# Sij.net
KiCad netlist of a schematic drawn in EAGLE
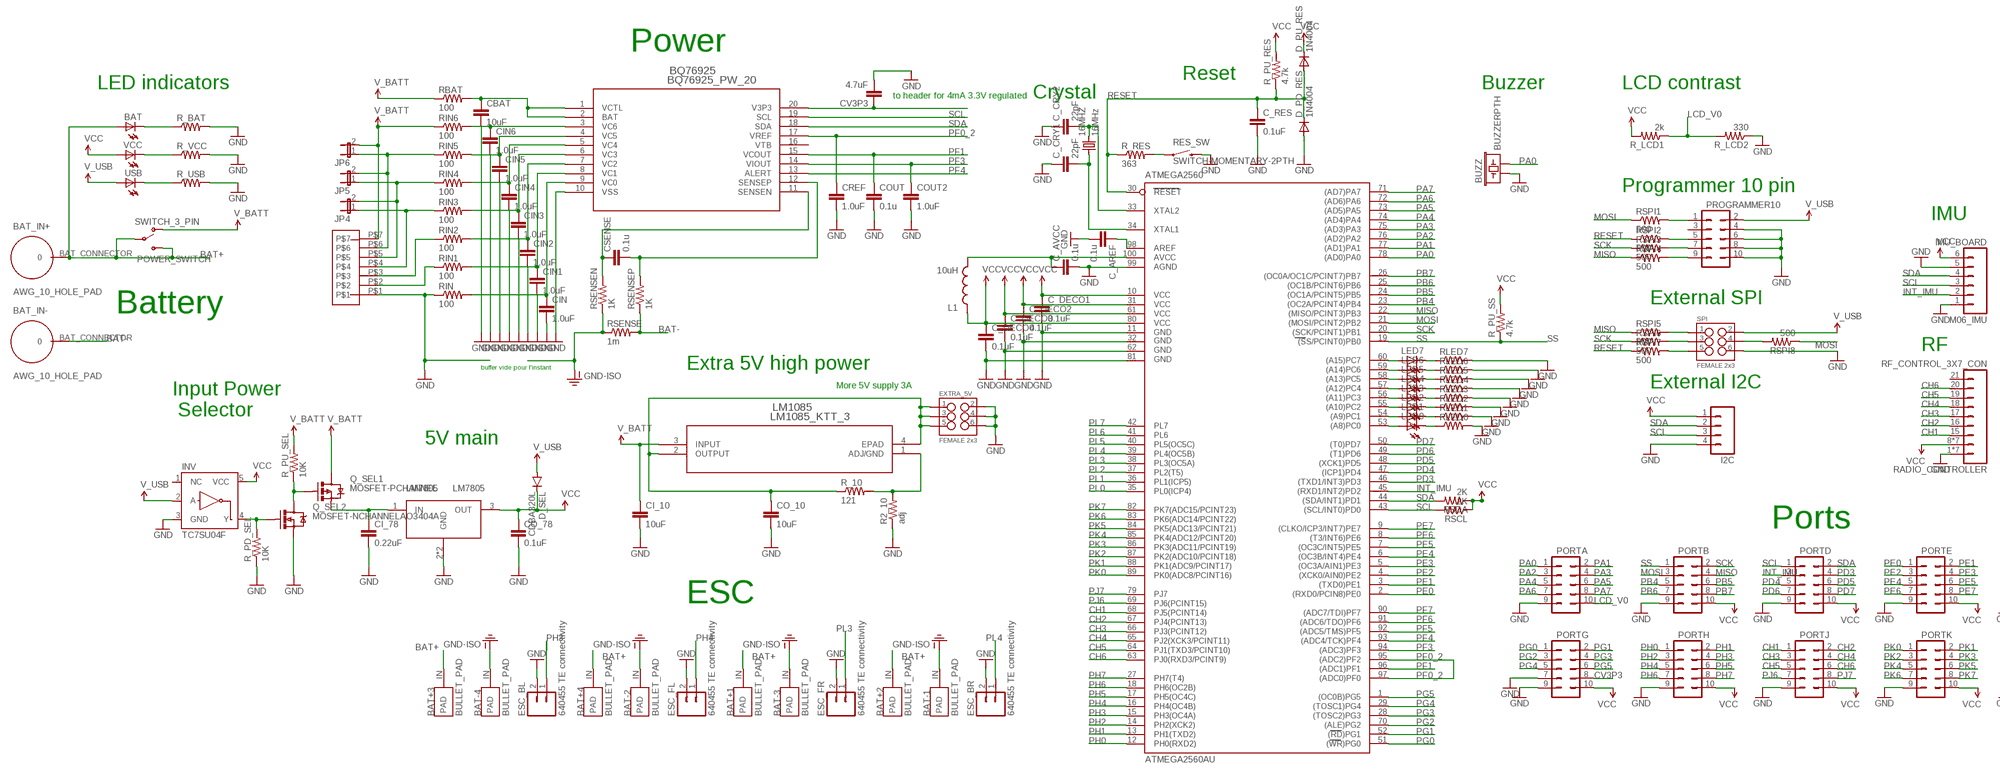
[diagram p0: schematic, sheet 1, part 1 of 2]
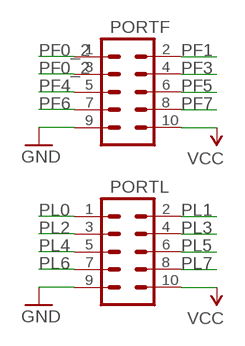
[diagram p1: schematic, sheet 1, part 2 of 2]

(export (version "E")
  (design (tool "Eeschema 10.0.6"))
  (components
    (comp (ref "16MHZ")
      (value "16MHz")
      (footprint "eagle-import:HC49US")
      (libsource (lib "eagle-import") (part "CRYSTALHC49US"))
    )
    (comp (ref "ATMEGA2560")
      (value "ATMEGA2560AU")
      (footprint "eagle-import:TQFP100")
      (libsource (lib "eagle-import") (part "ATMEGA2560AU"))
    )
    (comp (ref "BAT")
      (value "LEDCHIPLED_0805")
      (footprint "eagle-import:CHIPLED_0805")
      (libsource (lib "eagle-import") (part "LEDCHIPLED_0805"))
    )
    (comp (ref "BAT+1")
      (value "BULLET_PAD")
      (footprint "eagle-import:4.5MM_SQUARE")
      (libsource (lib "eagle-import") (part "BULLET_PAD"))
    )
    (comp (ref "BAT+2")
      (value "BULLET_PAD")
      (footprint "eagle-import:4.5MM_SQUARE")
      (libsource (lib "eagle-import") (part "BULLET_PAD"))
    )
    (comp (ref "BAT+3")
      (value "BULLET_PAD")
      (footprint "eagle-import:4.5MM_SQUARE")
      (libsource (lib "eagle-import") (part "BULLET_PAD"))
    )
    (comp (ref "BAT+4")
      (value "BULLET_PAD")
      (footprint "eagle-import:4.5MM_SQUARE")
      (libsource (lib "eagle-import") (part "BULLET_PAD"))
    )
    (comp (ref "BAT-1")
      (value "BULLET_PAD")
      (footprint "eagle-import:4.5MM_SQUARE")
      (libsource (lib "eagle-import") (part "BULLET_PAD"))
    )
    (comp (ref "BAT-2")
      (value "BULLET_PAD")
      (footprint "eagle-import:4.5MM_SQUARE")
      (libsource (lib "eagle-import") (part "BULLET_PAD"))
    )
    (comp (ref "BAT-3")
      (value "BULLET_PAD")
      (footprint "eagle-import:4.5MM_SQUARE")
      (libsource (lib "eagle-import") (part "BULLET_PAD"))
    )
    (comp (ref "BAT-4")
      (value "BULLET_PAD")
      (footprint "eagle-import:4.5MM_SQUARE")
      (libsource (lib "eagle-import") (part "BULLET_PAD"))
    )
    (comp (ref "BAT-MONIT")
      (value "7_PIN_JST-XH")
      (footprint "eagle-import:7_PIN_JST-XH")
      (libsource (lib "eagle-import") (part "7_PIN_JST-XH"))
    )
    (comp (ref "BAT_IN+")
      (value "AWG_10_HOLE_PAD")
      (footprint "eagle-import:AWG10_HOLE_PAD")
      (libsource (lib "eagle-import") (part "AWG_10_HOLE_PAD"))
    )
    (comp (ref "BAT_IN-")
      (value "AWG_10_HOLE_PAD")
      (footprint "eagle-import:AWG10_HOLE_PAD")
      (libsource (lib "eagle-import") (part "AWG_10_HOLE_PAD"))
    )
    (comp (ref "BQ76925")
      (value "BQ76925_PW_20")
      (footprint "eagle-import:PW20")
      (fields
        (field (name "GENERIC_PART_NUMBER") "BQ76925")
        (field (name "MANUFACTURER") "Texas Instruments")
        (field (name "MANUFACTURER_PART_NUMBER") "bq76925_pw_20")
      )
      (libsource (lib "eagle-import") (part "BQ76925_PW_20"))
    )
    (comp (ref "BUZZ")
      (value "BUZZERPTH")
      (footprint "eagle-import:BUZZER-12MM")
      (libsource (lib "eagle-import") (part "BUZZERPTH"))
    )
    (comp (ref "CBAT")
      (value "10uF")
      (footprint "eagle-import:0805")
      (libsource (lib "eagle-import") (part "CAP0805"))
    )
    (comp (ref "CIN")
      (value "1.0uF")
      (footprint "eagle-import:0603-CAP")
      (libsource (lib "eagle-import") (part "1.0UF-16V-10%(0603)"))
    )
    (comp (ref "CIN1")
      (value "1.0uF")
      (footprint "eagle-import:0603-CAP")
      (libsource (lib "eagle-import") (part "1.0UF-16V-10%(0603)"))
    )
    (comp (ref "CIN2")
      (value "1.0uF")
      (footprint "eagle-import:0603-CAP")
      (libsource (lib "eagle-import") (part "1.0UF-16V-10%(0603)"))
    )
    (comp (ref "CIN3")
      (value "1.0uF")
      (footprint "eagle-import:0603-CAP")
      (libsource (lib "eagle-import") (part "1.0UF-16V-10%(0603)"))
    )
    (comp (ref "CIN4")
      (value "1.0uF")
      (footprint "eagle-import:0603-CAP")
      (libsource (lib "eagle-import") (part "1.0UF-16V-10%(0603)"))
    )
    (comp (ref "CIN5")
      (value "1.0uF")
      (footprint "eagle-import:0603-CAP")
      (libsource (lib "eagle-import") (part "1.0UF-16V-10%(0603)"))
    )
    (comp (ref "CIN6")
      (value "1.0uF")
      (footprint "eagle-import:0603-CAP")
      (libsource (lib "eagle-import") (part "1.0UF-16V-10%(0603)"))
    )
    (comp (ref "CI_10")
      (value "10uF")
      (footprint "eagle-import:0805")
      (libsource (lib "eagle-import") (part "22UF-6.3V-20%(0805)"))
    )
    (comp (ref "CI_78")
      (value "0.22uF")
      (footprint "eagle-import:0603-CAP")
      (libsource (lib "eagle-import") (part "0.22UF-25V-10%(0603)"))
    )
    (comp (ref "COUT")
      (value "0.1u")
      (footprint "eagle-import:0603-CAP")
      (libsource (lib "eagle-import") (part "CAP0603-CAP"))
    )
    (comp (ref "COUT2")
      (value "1.0uF")
      (footprint "eagle-import:0603-CAP")
      (libsource (lib "eagle-import") (part "1.0UF-16V-10%(0603)"))
    )
    (comp (ref "CO_10")
      (value "10uF")
      (footprint "eagle-import:1206")
      (libsource (lib "eagle-import") (part "CAP1206"))
    )
    (comp (ref "CO_78")
      (value "0.1uF")
      (footprint "eagle-import:0603-CAP")
      (libsource (lib "eagle-import") (part "0.1UF-25V-5%(0603)"))
    )
    (comp (ref "CREF")
      (value "1.0uF")
      (footprint "eagle-import:0603-CAP")
      (libsource (lib "eagle-import") (part "1.0UF-16V-10%(0603)"))
    )
    (comp (ref "CSENSE")
      (value "0.1u")
      (footprint "eagle-import:0603-CAP")
      (libsource (lib "eagle-import") (part "SparkFun-Passives_CAP0603-CAP"))
    )
    (comp (ref "CV3P3")
      (value "4.7uF")
      (footprint "eagle-import:0603-CAP")
      (libsource (lib "eagle-import") (part "4.7UF-6.3V-10%(0603)0603"))
    )
    (comp (ref "C_AREF")
      (value "0.1u")
      (footprint "eagle-import:0603-CAP")
      (libsource (lib "eagle-import") (part "CAP0603-CAP"))
    )
    (comp (ref "C_AVCC")
      (value "0.1u")
      (footprint "eagle-import:0603-CAP")
      (libsource (lib "eagle-import") (part "CAP0603-CAP"))
    )
    (comp (ref "C_CRY1")
      (value "22pF")
      (footprint "eagle-import:0603-CAP")
      (libsource (lib "eagle-import") (part "22PF-50V-5%(0603)"))
    )
    (comp (ref "C_CRY2")
      (value "22pF")
      (footprint "eagle-import:0603-CAP")
      (libsource (lib "eagle-import") (part "22PF-50V-5%(0603)"))
    )
    (comp (ref "C_DECO1")
      (value "0.1uF")
      (footprint "eagle-import:0603-CAP")
      (libsource (lib "eagle-import") (part "0.1UF-25V-5%(0603)"))
    )
    (comp (ref "C_DECO2")
      (value "0.1uF")
      (footprint "eagle-import:0603-CAP")
      (libsource (lib "eagle-import") (part "0.1UF-25V-5%(0603)"))
    )
    (comp (ref "C_DECO3")
      (value "0.1uF")
      (footprint "eagle-import:0603-CAP")
      (libsource (lib "eagle-import") (part "0.1UF-25V-5%(0603)"))
    )
    (comp (ref "C_DECO4")
      (value "0.1uF")
      (footprint "eagle-import:0603-CAP")
      (libsource (lib "eagle-import") (part "0.1UF-25V-5%(0603)"))
    )
    (comp (ref "C_RES")
      (value "0.1uF")
      (footprint "eagle-import:0603-CAP")
      (libsource (lib "eagle-import") (part "0.1UF-25V-5%(0603)"))
    )
    (comp (ref "D_PD_RES")
      (value "1N4004")
      (footprint "eagle-import:DO41-10")
      (libsource (lib "eagle-import") (part "1N4004"))
    )
    (comp (ref "D_PU_RES")
      (value "1N4004")
      (footprint "eagle-import:DO41-10")
      (libsource (lib "eagle-import") (part "1N4004"))
    )
    (comp (ref "D_SEL")
      (value "CDBA320L")
      (footprint "eagle-import:SMA-DIODE_ALT")
      (libsource (lib "eagle-import") (part "DIODESMA-ALT"))
    )
    (comp (ref "ESC_BL")
      (value "640455 TE connectivity")
      (footprint "eagle-import:1X02")
      (libsource (lib "eagle-import") (part "M02PTH"))
    )
    (comp (ref "ESC_BR")
      (value "640455 TE connectivity")
      (footprint "eagle-import:1X02")
      (libsource (lib "eagle-import") (part "M02PTH"))
    )
    (comp (ref "ESC_FL")
      (value "640455 TE connectivity")
      (footprint "eagle-import:1X02")
      (libsource (lib "eagle-import") (part "M02PTH"))
    )
    (comp (ref "ESC_FR")
      (value "640455 TE connectivity")
      (footprint "eagle-import:1X02")
      (libsource (lib "eagle-import") (part "M02PTH"))
    )
    (comp (ref "EXTRA_5V")
      (value "FEMALE 2x3")
      (footprint "eagle-import:2X3")
      (libsource (lib "eagle-import") (part "M03X2FEMALE"))
    )
    (comp (ref "I2C")
      (value "M041X04_NO_SILK")
      (footprint "eagle-import:1X04_NO_SILK")
      (libsource (lib "eagle-import") (part "M041X04_NO_SILK"))
    )
    (comp (ref "IMU_BOARD")
      (value "M06_IMU")
      (footprint "eagle-import:1X06_LONGPADS")
      (libsource (lib "eagle-import") (part "M06_IMU"))
    )
    (comp (ref "INV")
      (value "TC7SU04F")
      (footprint "eagle-import:SOT23-5")
      (libsource (lib "eagle-import") (part "INVERTER_SOT23-5"))
    )
    (comp (ref "JP4")
      (value "JUMPER-2PTH")
      (footprint "eagle-import:1X02")
      (libsource (lib "eagle-import") (part "JUMPER-2PTH"))
    )
    (comp (ref "JP5")
      (value "JUMPER-2PTH")
      (footprint "eagle-import:1X02")
      (libsource (lib "eagle-import") (part "JUMPER-2PTH"))
    )
    (comp (ref "JP6")
      (value "JUMPER-2PTH")
      (footprint "eagle-import:1X02")
      (libsource (lib "eagle-import") (part "JUMPER-2PTH"))
    )
    (comp (ref "L1")
      (value "10uH")
      (footprint "eagle-import:0805")
      (libsource (lib "eagle-import") (part "INDUCTOR0805"))
    )
    (comp (ref "LED0")
      (value "LEDCHIPLED_0805")
      (footprint "eagle-import:CHIPLED_0805")
      (libsource (lib "eagle-import") (part "LEDCHIPLED_0805"))
    )
    (comp (ref "LED1")
      (value "LEDCHIPLED_0805")
      (footprint "eagle-import:CHIPLED_0805")
      (libsource (lib "eagle-import") (part "LEDCHIPLED_0805"))
    )
    (comp (ref "LED2")
      (value "LEDCHIPLED_0805")
      (footprint "eagle-import:CHIPLED_0805")
      (libsource (lib "eagle-import") (part "LEDCHIPLED_0805"))
    )
    (comp (ref "LED3")
      (value "LEDCHIPLED_0805")
      (footprint "eagle-import:CHIPLED_0805")
      (libsource (lib "eagle-import") (part "LEDCHIPLED_0805"))
    )
    (comp (ref "LED4")
      (value "LEDCHIPLED_0805")
      (footprint "eagle-import:CHIPLED_0805")
      (libsource (lib "eagle-import") (part "LEDCHIPLED_0805"))
    )
    (comp (ref "LED5")
      (value "LEDCHIPLED_0805")
      (footprint "eagle-import:CHIPLED_0805")
      (libsource (lib "eagle-import") (part "LEDCHIPLED_0805"))
    )
    (comp (ref "LED6")
      (value "LEDCHIPLED_0805")
      (footprint "eagle-import:CHIPLED_0805")
      (libsource (lib "eagle-import") (part "LEDCHIPLED_0805"))
    )
    (comp (ref "LED7")
      (value "LEDCHIPLED_0805")
      (footprint "eagle-import:CHIPLED_0805")
      (libsource (lib "eagle-import") (part "LEDCHIPLED_0805"))
    )
    (comp (ref "LM1085")
      (value "LM1085_KTT_3")
      (footprint "eagle-import:KTT3")
      (fields (field (name "MANUFACTURER_PART_NUMBER") "lm1085_ktt_3"))
      (libsource (lib "eagle-import") (part "LM1085_KTT_3"))
    )
    (comp (ref "LM7805")
      (value "LM7805")
      (footprint "eagle-import:KTT3")
      (libsource (lib "eagle-import") (part "LM7805"))
    )
    (comp (ref "PORTA")
      (value "M05X2PTH")
      (footprint "eagle-import:AVR_ICSP")
      (libsource (lib "eagle-import") (part "M05X2PTH"))
    )
    (comp (ref "PORTB")
      (value "M05X2PTH")
      (footprint "eagle-import:AVR_ICSP")
      (libsource (lib "eagle-import") (part "M05X2PTH"))
    )
    (comp (ref "PORTD")
      (value "M05X2PTH")
      (footprint "eagle-import:AVR_ICSP")
      (libsource (lib "eagle-import") (part "M05X2PTH"))
    )
    (comp (ref "PORTE")
      (value "M05X2PTH")
      (footprint "eagle-import:AVR_ICSP")
      (libsource (lib "eagle-import") (part "M05X2PTH"))
    )
    (comp (ref "PORTF")
      (value "M05X2PTH")
      (footprint "eagle-import:AVR_ICSP")
      (libsource (lib "eagle-import") (part "M05X2PTH"))
    )
    (comp (ref "PORTG")
      (value "M05X2PTH")
      (footprint "eagle-import:AVR_ICSP")
      (libsource (lib "eagle-import") (part "M05X2PTH"))
    )
    (comp (ref "PORTH")
      (value "M05X2PTH")
      (footprint "eagle-import:AVR_ICSP")
      (libsource (lib "eagle-import") (part "M05X2PTH"))
    )
    (comp (ref "PORTJ")
      (value "M05X2PTH")
      (footprint "eagle-import:AVR_ICSP")
      (libsource (lib "eagle-import") (part "M05X2PTH"))
    )
    (comp (ref "PORTK")
      (value "M05X2PTH")
      (footprint "eagle-import:AVR_ICSP")
      (libsource (lib "eagle-import") (part "M05X2PTH"))
    )
    (comp (ref "PORTL")
      (value "M05X2PTH")
      (footprint "eagle-import:AVR_ICSP")
      (libsource (lib "eagle-import") (part "M05X2PTH"))
    )
    (comp (ref "POWER_SWITCH")
      (value "SWITCH_3_PIN")
      (footprint "eagle-import:SWITCH-SPDT_KIT")
      (libsource (lib "eagle-import") (part "SWITCH_3_PIN"))
    )
    (comp (ref "PROGRAMMER10")
      (value "M05X2PTH")
      (footprint "eagle-import:AVR_ICSP")
      (libsource (lib "eagle-import") (part "M05X2PTH"))
    )
    (comp (ref "Q_SEL1")
      (value "MOSFET-PCHANNEL")
      (footprint "eagle-import:SOT23-3")
      (libsource (lib "eagle-import") (part "MOSFET-PCHANNEL"))
    )
    (comp (ref "Q_SEL2")
      (value "MOSFET-NCHANNELAO3404A")
      (footprint "eagle-import:SOT23-3")
      (libsource (lib "eagle-import") (part "MOSFET-NCHANNELAO3404A"))
    )
    (comp (ref "R2_10")
      (value "adj")
      (footprint "eagle-import:R0603")
      (libsource (lib "eagle-import") (part "R-US_R0603"))
    )
    (comp (ref "RADIO_CONTROLLER")
      (value "RF_CONTROL_3X7_CON")
      (footprint "eagle-import:3X07")
      (libsource (lib "eagle-import") (part "RF_CONTROL_3X7_CON"))
    )
    (comp (ref "RBAT")
      (value "100")
      (footprint "eagle-import:R0603")
      (libsource (lib "eagle-import") (part "R-US_R0603"))
    )
    (comp (ref "RES_SW")
      (value "SWITCH-MOMENTARY-2PTH")
      (footprint "eagle-import:TACTILE-PTH")
      (libsource (lib "eagle-import") (part "SWITCH-MOMENTARY-2PTH"))
    )
    (comp (ref "RIN")
      (value "100")
      (footprint "eagle-import:R0603")
      (libsource (lib "eagle-import") (part "R-US_R0603"))
    )
    (comp (ref "RIN1")
      (value "100")
      (footprint "eagle-import:R0603")
      (libsource (lib "eagle-import") (part "R-US_R0603"))
    )
    (comp (ref "RIN2")
      (value "100")
      (footprint "eagle-import:R0603")
      (libsource (lib "eagle-import") (part "R-US_R0603"))
    )
    (comp (ref "RIN3")
      (value "100")
      (footprint "eagle-import:R0603")
      (libsource (lib "eagle-import") (part "R-US_R0603"))
    )
    (comp (ref "RIN4")
      (value "100")
      (footprint "eagle-import:R0603")
      (libsource (lib "eagle-import") (part "R-US_R0603"))
    )
    (comp (ref "RIN5")
      (value "100")
      (footprint "eagle-import:R0603")
      (libsource (lib "eagle-import") (part "R-US_R0603"))
    )
    (comp (ref "RIN6")
      (value "100")
      (footprint "eagle-import:R0603")
      (libsource (lib "eagle-import") (part "R-US_R0603"))
    )
    (comp (ref "RLED0")
      (value "R-US_R0603")
      (footprint "eagle-import:R0603")
      (libsource (lib "eagle-import") (part "R-US_R0603"))
    )
    (comp (ref "RLED1")
      (value "R-US_R0603")
      (footprint "eagle-import:R0603")
      (libsource (lib "eagle-import") (part "R-US_R0603"))
    )
    (comp (ref "RLED2")
      (value "R-US_R0603")
      (footprint "eagle-import:R0603")
      (libsource (lib "eagle-import") (part "R-US_R0603"))
    )
    (comp (ref "RLED3")
      (value "R-US_R0603")
      (footprint "eagle-import:R0603")
      (libsource (lib "eagle-import") (part "R-US_R0603"))
    )
    (comp (ref "RLED4")
      (value "R-US_R0603")
      (footprint "eagle-import:R0603")
      (libsource (lib "eagle-import") (part "R-US_R0603"))
    )
    (comp (ref "RLED5")
      (value "R-US_R0603")
      (footprint "eagle-import:R0603")
      (libsource (lib "eagle-import") (part "R-US_R0603"))
    )
    (comp (ref "RLED6")
      (value "R-US_R0603")
      (footprint "eagle-import:R0603")
      (libsource (lib "eagle-import") (part "R-US_R0603"))
    )
    (comp (ref "RLED7")
      (value "R-US_R0603")
      (footprint "eagle-import:R0603")
      (libsource (lib "eagle-import") (part "R-US_R0603"))
    )
    (comp (ref "RSCL")
      (value "2K")
      (footprint "eagle-import:R0603")
      (libsource (lib "eagle-import") (part "R-US_R0603"))
    )
    (comp (ref "RSDA")
      (value "2K")
      (footprint "eagle-import:R0603")
      (libsource (lib "eagle-import") (part "R-US_R0603"))
    )
    (comp (ref "RSENSE")
      (value "1m")
      (footprint "eagle-import:R1206")
      (libsource (lib "eagle-import") (part "R-US_R1206"))
    )
    (comp (ref "RSENSEN")
      (value "1K")
      (footprint "eagle-import:R0603")
      (libsource (lib "eagle-import") (part "R-US_R0603"))
    )
    (comp (ref "RSENSEP")
      (value "1K")
      (footprint "eagle-import:R0603")
      (libsource (lib "eagle-import") (part "R-US_R0603"))
    )
    (comp (ref "RSPI1")
      (value "500")
      (footprint "eagle-import:R0603")
      (libsource (lib "eagle-import") (part "R-US_R0603"))
    )
    (comp (ref "RSPI2")
      (value "500")
      (footprint "eagle-import:R0603")
      (libsource (lib "eagle-import") (part "R-US_R0603"))
    )
    (comp (ref "RSPI3")
      (value "500")
      (footprint "eagle-import:R0603")
      (libsource (lib "eagle-import") (part "R-US_R0603"))
    )
    (comp (ref "RSPI4")
      (value "500")
      (footprint "eagle-import:R0603")
      (libsource (lib "eagle-import") (part "R-US_R0603"))
    )
    (comp (ref "RSPI5")
      (value "500")
      (footprint "eagle-import:R0603")
      (libsource (lib "eagle-import") (part "R-US_R0603"))
    )
    (comp (ref "RSPI6")
      (value "500")
      (footprint "eagle-import:R0603")
      (libsource (lib "eagle-import") (part "R-US_R0603"))
    )
    (comp (ref "RSPI7")
      (value "500")
      (footprint "eagle-import:R0603")
      (libsource (lib "eagle-import") (part "R-US_R0603"))
    )
    (comp (ref "RSPI8")
      (value "500")
      (footprint "eagle-import:R0603")
      (libsource (lib "eagle-import") (part "R-US_R0603"))
    )
    (comp (ref "R_10")
      (value "121")
      (footprint "eagle-import:R0603")
      (libsource (lib "eagle-import") (part "R-US_R0603"))
    )
    (comp (ref "R_BAT")
      (value "R-US_R0603")
      (footprint "eagle-import:R0603")
      (libsource (lib "eagle-import") (part "R-US_R0603"))
    )
    (comp (ref "R_LCD1")
      (value "2k")
      (footprint "eagle-import:R0603")
      (libsource (lib "eagle-import") (part "R-US_R0603"))
    )
    (comp (ref "R_LCD2")
      (value "330")
      (footprint "eagle-import:R0603")
      (libsource (lib "eagle-import") (part "R-US_R0603"))
    )
    (comp (ref "R_PD_SEL")
      (value "10K")
      (footprint "eagle-import:R0603")
      (libsource (lib "eagle-import") (part "R-US_R0603"))
    )
    (comp (ref "R_PU_RES")
      (value "4.7k")
      (footprint "eagle-import:R0603")
      (libsource (lib "eagle-import") (part "R-US_R0603"))
    )
    (comp (ref "R_PU_SEL")
      (value "10K")
      (footprint "eagle-import:R0603")
      (libsource (lib "eagle-import") (part "R-US_R0603"))
    )
    (comp (ref "R_PU_SS")
      (value "4.7k")
      (footprint "eagle-import:R0603")
      (libsource (lib "eagle-import") (part "R-US_R0603"))
    )
    (comp (ref "R_RES")
      (value "363")
      (footprint "eagle-import:R0603")
      (libsource (lib "eagle-import") (part "R-US_R0603"))
    )
    (comp (ref "R_USB")
      (value "R-US_R0603")
      (footprint "eagle-import:R0603")
      (libsource (lib "eagle-import") (part "R-US_R0603"))
    )
    (comp (ref "R_VCC")
      (value "R-US_R0603")
      (footprint "eagle-import:R0603")
      (libsource (lib "eagle-import") (part "R-US_R0603"))
    )
    (comp (ref "SPI")
      (value "FEMALE 2x3")
      (footprint "eagle-import:2X3")
      (libsource (lib "eagle-import") (part "M03X2FEMALE"))
    )
    (comp (ref "USB")
      (value "LEDCHIPLED_0805")
      (footprint "eagle-import:CHIPLED_0805")
      (libsource (lib "eagle-import") (part "LEDCHIPLED_0805"))
    )
    (comp (ref "VCC")
      (value "LEDCHIPLED_0805")
      (footprint "eagle-import:CHIPLED_0805")
      (libsource (lib "eagle-import") (part "LEDCHIPLED_0805"))
    )
  )
  (nets
    (net (code "1") (name "/BAT+") (class "Default")
      (node (ref "BAT") (pin "A") (pinfunction "A_A") (pintype "passive"))
      (node (ref "BAT+1") (pin "IN") (pinfunction "PAD_IN") (pintype "bidirectional"))
      (node (ref "BAT+2") (pin "IN") (pinfunction "PAD_IN") (pintype "bidirectional"))
      (node (ref "BAT+3") (pin "IN") (pinfunction "PAD_IN") (pintype "bidirectional"))
      (node (ref "BAT+4") (pin "IN") (pinfunction "PAD_IN") (pintype "bidirectional"))
      (node (ref "BAT_IN+") (pin "BAT_CONNECTOR") (pinfunction "0_BAT_CONNECTOR") (pintype "bidirectional"))
      (node (ref "POWER_SWITCH") (pin "2") (pinfunction "P_2") (pintype "passive"))
      (node (ref "POWER_SWITCH") (pin "3") (pinfunction "S_3") (pintype "passive"))
    )
    (net (code "2") (name "/BAT-") (class "Default")
      (node (ref "BAT_IN-") (pin "BAT_CONNECTOR") (pinfunction "0_BAT_CONNECTOR") (pintype "bidirectional"))
      (node (ref "RSENSE") (pin "2") (pinfunction "2_2") (pintype "passive"))
      (node (ref "RSENSEP") (pin "1") (pinfunction "1_1") (pintype "passive"))
    )
    (net (code "3") (name "/CH1") (class "Default")
      (node (ref "ATMEGA2560") (pin "68") (pinfunction "PJ5(PCINT14)_68") (pintype "bidirectional"))
      (node (ref "PORTJ") (pin "1") (pinfunction "1_1") (pintype "passive"))
      (node (ref "RADIO_CONTROLLER") (pin "15") (pinfunction "1_15") (pintype "bidirectional"))
    )
    (net (code "4") (name "/CH2") (class "Default")
      (node (ref "ATMEGA2560") (pin "67") (pinfunction "PJ4(PCINT13)_67") (pintype "bidirectional"))
      (node (ref "PORTJ") (pin "2") (pinfunction "2_2") (pintype "passive"))
      (node (ref "RADIO_CONTROLLER") (pin "16") (pinfunction "2_16") (pintype "bidirectional"))
    )
    (net (code "5") (name "/CH3") (class "Default")
      (node (ref "ATMEGA2560") (pin "66") (pinfunction "PJ3(PCINT12)_66") (pintype "bidirectional"))
      (node (ref "PORTJ") (pin "3") (pinfunction "3_3") (pintype "passive"))
      (node (ref "RADIO_CONTROLLER") (pin "17") (pinfunction "3_17") (pintype "bidirectional"))
    )
    (net (code "6") (name "/CH4") (class "Default")
      (node (ref "ATMEGA2560") (pin "65") (pinfunction "PJ2(XCK3/PCINT11)_65") (pintype "bidirectional"))
      (node (ref "PORTJ") (pin "4") (pinfunction "4_4") (pintype "passive"))
      (node (ref "RADIO_CONTROLLER") (pin "18") (pinfunction "4_18") (pintype "bidirectional"))
    )
    (net (code "7") (name "/CH5") (class "Default")
      (node (ref "ATMEGA2560") (pin "64") (pinfunction "PJ1(TXD3/PCINT10)_64") (pintype "bidirectional"))
      (node (ref "PORTJ") (pin "5") (pinfunction "5_5") (pintype "passive"))
      (node (ref "RADIO_CONTROLLER") (pin "19") (pinfunction "5_19") (pintype "bidirectional"))
    )
    (net (code "8") (name "/CH6") (class "Default")
      (node (ref "ATMEGA2560") (pin "63") (pinfunction "PJ0(RXD3/PCINT9)_63") (pintype "bidirectional"))
      (node (ref "PORTJ") (pin "6") (pinfunction "6_6") (pintype "passive"))
      (node (ref "RADIO_CONTROLLER") (pin "20") (pinfunction "6_20") (pintype "bidirectional"))
    )
    (net (code "9") (name "/CV3P3") (class "Default")
      (node (ref "BQ76925") (pin "20") (pinfunction "V3P3_20") (pintype "output"))
      (node (ref "CV3P3") (pin "1") (pinfunction "1_1") (pintype "passive"))
      (node (ref "PORTG") (pin "8") (pinfunction "8_8") (pintype "passive"))
    )
    (net (code "10") (name "/INT_IMU") (class "Default")
      (node (ref "ATMEGA2560") (pin "45") (pinfunction "(RXD1/INT2)PD2_45") (pintype "bidirectional"))
      (node (ref "IMU_BOARD") (pin "2") (pinfunction "2_2") (pintype "passive"))
      (node (ref "PORTD") (pin "3") (pinfunction "3_3") (pintype "passive"))
    )
    (net (code "11") (name "/LCD_V0") (class "Default")
      (node (ref "PORTA") (pin "10") (pinfunction "10_10") (pintype "passive"))
      (node (ref "R_LCD1") (pin "1") (pinfunction "1_1") (pintype "passive"))
      (node (ref "R_LCD2") (pin "2") (pinfunction "2_2") (pintype "passive"))
    )
    (net (code "12") (name "/MISO") (class "Default")
      (node (ref "ATMEGA2560") (pin "22") (pinfunction "(MISO/PCINT3)PB3_22") (pintype "bidirectional"))
      (node (ref "PORTB") (pin "4") (pinfunction "4_4") (pintype "passive"))
      (node (ref "RSPI4") (pin "1") (pinfunction "1_1") (pintype "passive"))
      (node (ref "RSPI5") (pin "1") (pinfunction "1_1") (pintype "passive"))
    )
    (net (code "13") (name "/MOSI") (class "Default")
      (node (ref "ATMEGA2560") (pin "21") (pinfunction "(MOSI/PCINT2)PB2_21") (pintype "bidirectional"))
      (node (ref "PORTB") (pin "3") (pinfunction "3_3") (pintype "passive"))
      (node (ref "RSPI1") (pin "1") (pinfunction "1_1") (pintype "passive"))
      (node (ref "RSPI8") (pin "1") (pinfunction "1_1") (pintype "passive"))
    )
    (net (code "14") (name "/PA0") (class "Default")
      (node (ref "ATMEGA2560") (pin "78") (pinfunction "(AD0)PA0_78") (pintype "bidirectional"))
      (node (ref "BUZZ") (pin "-") (pinfunction "2_-") (pintype "passive"))
      (node (ref "PORTA") (pin "1") (pinfunction "1_1") (pintype "passive"))
    )
    (net (code "15") (name "/PA1") (class "Default")
      (node (ref "ATMEGA2560") (pin "77") (pinfunction "(AD1)PA1_77") (pintype "bidirectional"))
      (node (ref "PORTA") (pin "2") (pinfunction "2_2") (pintype "passive"))
    )
    (net (code "16") (name "/PA2") (class "Default")
      (node (ref "ATMEGA2560") (pin "76") (pinfunction "(AD2)PA2_76") (pintype "bidirectional"))
      (node (ref "PORTA") (pin "3") (pinfunction "3_3") (pintype "passive"))
    )
    (net (code "17") (name "/PA3") (class "Default")
      (node (ref "ATMEGA2560") (pin "75") (pinfunction "(AD3)PA3_75") (pintype "bidirectional"))
      (node (ref "PORTA") (pin "4") (pinfunction "4_4") (pintype "passive"))
    )
    (net (code "18") (name "/PA4") (class "Default")
      (node (ref "ATMEGA2560") (pin "74") (pinfunction "(AD4)PA4_74") (pintype "bidirectional"))
      (node (ref "PORTA") (pin "5") (pinfunction "5_5") (pintype "passive"))
    )
    (net (code "19") (name "/PA5") (class "Default")
      (node (ref "ATMEGA2560") (pin "73") (pinfunction "(AD5)PA5_73") (pintype "bidirectional"))
      (node (ref "PORTA") (pin "6") (pinfunction "6_6") (pintype "passive"))
    )
    (net (code "20") (name "/PA6") (class "Default")
      (node (ref "ATMEGA2560") (pin "72") (pinfunction "(AD6)PA6_72") (pintype "bidirectional"))
      (node (ref "PORTA") (pin "7") (pinfunction "7_7") (pintype "passive"))
    )
    (net (code "21") (name "/PA7") (class "Default")
      (node (ref "ATMEGA2560") (pin "71") (pinfunction "(AD7)PA7_71") (pintype "bidirectional"))
      (node (ref "PORTA") (pin "8") (pinfunction "8_8") (pintype "passive"))
    )
    (net (code "22") (name "/PB4") (class "Default")
      (node (ref "ATMEGA2560") (pin "23") (pinfunction "(OC2A/PCINT4)PB4_23") (pintype "bidirectional"))
      (node (ref "PORTB") (pin "5") (pinfunction "5_5") (pintype "passive"))
    )
    (net (code "23") (name "/PB5") (class "Default")
      (node (ref "ATMEGA2560") (pin "24") (pinfunction "(OC1A/PCINT5)PB5_24") (pintype "bidirectional"))
      (node (ref "PORTB") (pin "6") (pinfunction "6_6") (pintype "passive"))
    )
    (net (code "24") (name "/PB6") (class "Default")
      (node (ref "ATMEGA2560") (pin "25") (pinfunction "(OC1B/PCINT6)PB6_25") (pintype "bidirectional"))
      (node (ref "PORTB") (pin "7") (pinfunction "7_7") (pintype "passive"))
    )
    (net (code "25") (name "/PB7") (class "Default")
      (node (ref "ATMEGA2560") (pin "26") (pinfunction "(OC0A/OC1C/PCINT7)PB7_26") (pintype "bidirectional"))
      (node (ref "PORTB") (pin "8") (pinfunction "8_8") (pintype "passive"))
    )
    (net (code "26") (name "/PD3") (class "Default")
      (node (ref "ATMEGA2560") (pin "46") (pinfunction "(TXD1/INT3)PD3_46") (pintype "bidirectional"))
      (node (ref "PORTD") (pin "4") (pinfunction "4_4") (pintype "passive"))
    )
    (net (code "27") (name "/PD4") (class "Default")
      (node (ref "ATMEGA2560") (pin "47") (pinfunction "(ICP1)PD4_47") (pintype "bidirectional"))
      (node (ref "PORTD") (pin "5") (pinfunction "5_5") (pintype "passive"))
    )
    (net (code "28") (name "/PD5") (class "Default")
      (node (ref "ATMEGA2560") (pin "48") (pinfunction "(XCK1)PD5_48") (pintype "bidirectional"))
      (node (ref "PORTD") (pin "6") (pinfunction "6_6") (pintype "passive"))
    )
    (net (code "29") (name "/PD6") (class "Default")
      (node (ref "ATMEGA2560") (pin "49") (pinfunction "(T1)PD6_49") (pintype "bidirectional"))
      (node (ref "PORTD") (pin "7") (pinfunction "7_7") (pintype "passive"))
    )
    (net (code "30") (name "/PD7") (class "Default")
      (node (ref "ATMEGA2560") (pin "50") (pinfunction "(T0)PD7_50") (pintype "bidirectional"))
      (node (ref "PORTD") (pin "8") (pinfunction "8_8") (pintype "passive"))
    )
    (net (code "31") (name "/PE0") (class "Default")
      (node (ref "ATMEGA2560") (pin "2") (pinfunction "(RXD0/PCIN8)PE0_2") (pintype "bidirectional"))
      (node (ref "PORTE") (pin "1") (pinfunction "1_1") (pintype "passive"))
    )
    (net (code "32") (name "/PE1") (class "Default")
      (node (ref "ATMEGA2560") (pin "3") (pinfunction "(TXD0)PE1_3") (pintype "bidirectional"))
      (node (ref "PORTE") (pin "2") (pinfunction "2_2") (pintype "passive"))
    )
    (net (code "33") (name "/PE2") (class "Default")
      (node (ref "ATMEGA2560") (pin "4") (pinfunction "(XCK0/AIN0)PE2_4") (pintype "bidirectional"))
      (node (ref "PORTE") (pin "3") (pinfunction "3_3") (pintype "passive"))
    )
    (net (code "34") (name "/PE3") (class "Default")
      (node (ref "ATMEGA2560") (pin "5") (pinfunction "(OC3A/AIN1)PE3_5") (pintype "bidirectional"))
      (node (ref "PORTE") (pin "4") (pinfunction "4_4") (pintype "passive"))
    )
    (net (code "35") (name "/PE4") (class "Default")
      (node (ref "ATMEGA2560") (pin "6") (pinfunction "(OC3B/INT4)PE4_6") (pintype "bidirectional"))
      (node (ref "PORTE") (pin "5") (pinfunction "5_5") (pintype "passive"))
    )
    (net (code "36") (name "/PE5") (class "Default")
      (node (ref "ATMEGA2560") (pin "7") (pinfunction "(OC3C/INT5)PE5_7") (pintype "bidirectional"))
      (node (ref "PORTE") (pin "6") (pinfunction "6_6") (pintype "passive"))
    )
    (net (code "37") (name "/PE6") (class "Default")
      (node (ref "ATMEGA2560") (pin "8") (pinfunction "(T3/INT6)PE6_8") (pintype "bidirectional"))
      (node (ref "PORTE") (pin "7") (pinfunction "7_7") (pintype "passive"))
    )
    (net (code "38") (name "/PE7") (class "Default")
      (node (ref "ATMEGA2560") (pin "9") (pinfunction "(CLKO/ICP3/INT7)PE7_9") (pintype "bidirectional"))
      (node (ref "PORTE") (pin "8") (pinfunction "8_8") (pintype "passive"))
    )
    (net (code "39") (name "/PF0_2") (class "Default")
      (node (ref "ATMEGA2560") (pin "95") (pinfunction "(ADC2)PF2_95") (pintype "bidirectional"))
      (node (ref "ATMEGA2560") (pin "97") (pinfunction "(ADC0)PF0_97") (pintype "bidirectional"))
      (node (ref "BQ76925") (pin "17") (pinfunction "VREF_17") (pintype "output"))
      (node (ref "CREF") (pin "1") (pinfunction "1_1") (pintype "passive"))
      (node (ref "PORTF") (pin "1") (pinfunction "1_1") (pintype "passive"))
      (node (ref "PORTF") (pin "3") (pinfunction "3_3") (pintype "passive"))
    )
    (net (code "40") (name "/PF1") (class "Default")
      (node (ref "ATMEGA2560") (pin "96") (pinfunction "(ADC1)PF1_96") (pintype "bidirectional"))
      (node (ref "BQ76925") (pin "15") (pinfunction "VCOUT_15") (pintype "output"))
      (node (ref "COUT") (pin "1") (pinfunction "1_1") (pintype "passive"))
      (node (ref "PORTF") (pin "2") (pinfunction "2_2") (pintype "passive"))
    )
    (net (code "41") (name "/PF3") (class "Default")
      (node (ref "ATMEGA2560") (pin "94") (pinfunction "(ADC3)PF3_94") (pintype "bidirectional"))
      (node (ref "BQ76925") (pin "14") (pinfunction "VIOUT_14") (pintype "output"))
      (node (ref "COUT2") (pin "1") (pinfunction "1_1") (pintype "passive"))
      (node (ref "PORTF") (pin "4") (pinfunction "4_4") (pintype "passive"))
    )
    (net (code "42") (name "/PF4") (class "Default")
      (node (ref "ATMEGA2560") (pin "93") (pinfunction "(ADC4/TCK)PF4_93") (pintype "bidirectional"))
      (node (ref "BQ76925") (pin "13") (pinfunction "ALERT_13") (pintype "output"))
      (node (ref "PORTF") (pin "5") (pinfunction "5_5") (pintype "passive"))
    )
    (net (code "43") (name "/PF5") (class "Default")
      (node (ref "ATMEGA2560") (pin "92") (pinfunction "(ADC5/TMS)PF5_92") (pintype "bidirectional"))
      (node (ref "PORTF") (pin "6") (pinfunction "6_6") (pintype "passive"))
    )
    (net (code "44") (name "/PF6") (class "Default")
      (node (ref "ATMEGA2560") (pin "91") (pinfunction "(ADC6/TDO)PF6_91") (pintype "bidirectional"))
      (node (ref "PORTF") (pin "7") (pinfunction "7_7") (pintype "passive"))
    )
    (net (code "45") (name "/PF7") (class "Default")
      (node (ref "ATMEGA2560") (pin "90") (pinfunction "(ADC7/TDI)PF7_90") (pintype "bidirectional"))
      (node (ref "PORTF") (pin "8") (pinfunction "8_8") (pintype "passive"))
    )
    (net (code "46") (name "/PG0") (class "Default")
      (node (ref "ATMEGA2560") (pin "51") (pinfunction "(WR)PG0_51") (pintype "bidirectional"))
      (node (ref "PORTG") (pin "1") (pinfunction "1_1") (pintype "passive"))
    )
    (net (code "47") (name "/PG1") (class "Default")
      (node (ref "ATMEGA2560") (pin "52") (pinfunction "(RD)PG1_52") (pintype "bidirectional"))
      (node (ref "PORTG") (pin "2") (pinfunction "2_2") (pintype "passive"))
    )
    (net (code "48") (name "/PG2") (class "Default")
      (node (ref "ATMEGA2560") (pin "70") (pinfunction "(ALE)PG2_70") (pintype "bidirectional"))
      (node (ref "PORTG") (pin "3") (pinfunction "3_3") (pintype "passive"))
    )
    (net (code "49") (name "/PG3") (class "Default")
      (node (ref "ATMEGA2560") (pin "28") (pinfunction "(TOSC2)PG3_28") (pintype "bidirectional"))
      (node (ref "PORTG") (pin "4") (pinfunction "4_4") (pintype "passive"))
    )
    (net (code "50") (name "/PG4") (class "Default")
      (node (ref "ATMEGA2560") (pin "29") (pinfunction "(TOSC1)PG4_29") (pintype "bidirectional"))
      (node (ref "PORTG") (pin "5") (pinfunction "5_5") (pintype "passive"))
    )
    (net (code "51") (name "/PG5") (class "Default")
      (node (ref "ATMEGA2560") (pin "1") (pinfunction "(OC0B)PG5_1") (pintype "bidirectional"))
      (node (ref "PORTG") (pin "6") (pinfunction "6_6") (pintype "passive"))
    )
    (net (code "52") (name "/PH0") (class "Default")
      (node (ref "ATMEGA2560") (pin "12") (pinfunction "PH0(RXD2)_12") (pintype "bidirectional"))
      (node (ref "PORTH") (pin "1") (pinfunction "1_1") (pintype "passive"))
    )
    (net (code "53") (name "/PH1") (class "Default")
      (node (ref "ATMEGA2560") (pin "13") (pinfunction "PH1(TXD2)_13") (pintype "bidirectional"))
      (node (ref "PORTH") (pin "2") (pinfunction "2_2") (pintype "passive"))
    )
    (net (code "54") (name "/PH2") (class "Default")
      (node (ref "ATMEGA2560") (pin "14") (pinfunction "PH2(XCK2)_14") (pintype "bidirectional"))
      (node (ref "PORTH") (pin "3") (pinfunction "3_3") (pintype "passive"))
    )
    (net (code "55") (name "/PH3") (class "Default")
      (node (ref "ATMEGA2560") (pin "15") (pinfunction "PH3(OC4A)_15") (pintype "bidirectional"))
      (node (ref "ESC_BL") (pin "1") (pinfunction "1_1") (pintype "passive"))
      (node (ref "PORTH") (pin "4") (pinfunction "4_4") (pintype "passive"))
    )
    (net (code "56") (name "/PH4") (class "Default")
      (node (ref "ATMEGA2560") (pin "16") (pinfunction "PH4(OC4B)_16") (pintype "bidirectional"))
      (node (ref "ESC_FL") (pin "1") (pinfunction "1_1") (pintype "passive"))
      (node (ref "PORTH") (pin "5") (pinfunction "5_5") (pintype "passive"))
    )
    (net (code "57") (name "/PH5") (class "Default")
      (node (ref "ATMEGA2560") (pin "17") (pinfunction "PH5(OC4C)_17") (pintype "bidirectional"))
      (node (ref "PORTH") (pin "6") (pinfunction "6_6") (pintype "passive"))
    )
    (net (code "58") (name "/PH6") (class "Default")
      (node (ref "ATMEGA2560") (pin "18") (pinfunction "PH6(OC2B)_18") (pintype "bidirectional"))
      (node (ref "PORTH") (pin "7") (pinfunction "7_7") (pintype "passive"))
    )
    (net (code "59") (name "/PH7") (class "Default")
      (node (ref "ATMEGA2560") (pin "27") (pinfunction "PH7(T4)_27") (pintype "bidirectional"))
      (node (ref "PORTH") (pin "8") (pinfunction "8_8") (pintype "passive"))
    )
    (net (code "60") (name "/PJ6") (class "Default")
      (node (ref "ATMEGA2560") (pin "69") (pinfunction "PJ6(PCINT15)_69") (pintype "bidirectional"))
      (node (ref "PORTJ") (pin "7") (pinfunction "7_7") (pintype "passive"))
    )
    (net (code "61") (name "/PJ7") (class "Default")
      (node (ref "ATMEGA2560") (pin "79") (pinfunction "PJ7_79") (pintype "bidirectional"))
      (node (ref "PORTJ") (pin "8") (pinfunction "8_8") (pintype "passive"))
    )
    (net (code "62") (name "/PK0") (class "Default")
      (node (ref "ATMEGA2560") (pin "89") (pinfunction "PK0(ADC8/PCINT16)_89") (pintype "bidirectional"))
      (node (ref "PORTK") (pin "1") (pinfunction "1_1") (pintype "passive"))
    )
    (net (code "63") (name "/PK1") (class "Default")
      (node (ref "ATMEGA2560") (pin "88") (pinfunction "PK1(ADC9/PCINT17)_88") (pintype "bidirectional"))
      (node (ref "PORTK") (pin "2") (pinfunction "2_2") (pintype "passive"))
    )
    (net (code "64") (name "/PK2") (class "Default")
      (node (ref "ATMEGA2560") (pin "87") (pinfunction "PK2(ADC10/PCINT18)_87") (pintype "bidirectional"))
      (node (ref "PORTK") (pin "3") (pinfunction "3_3") (pintype "passive"))
    )
    (net (code "65") (name "/PK3") (class "Default")
      (node (ref "ATMEGA2560") (pin "86") (pinfunction "PK3(ADC11/PCINT19)_86") (pintype "bidirectional"))
      (node (ref "PORTK") (pin "4") (pinfunction "4_4") (pintype "passive"))
    )
    (net (code "66") (name "/PK4") (class "Default")
      (node (ref "ATMEGA2560") (pin "85") (pinfunction "PK4(ADC12/PCINT20)_85") (pintype "bidirectional"))
      (node (ref "PORTK") (pin "5") (pinfunction "5_5") (pintype "passive"))
    )
    (net (code "67") (name "/PK5") (class "Default")
      (node (ref "ATMEGA2560") (pin "84") (pinfunction "PK5(ADC13/PCINT21)_84") (pintype "bidirectional"))
      (node (ref "PORTK") (pin "6") (pinfunction "6_6") (pintype "passive"))
    )
    (net (code "68") (name "/PK6") (class "Default")
      (node (ref "ATMEGA2560") (pin "83") (pinfunction "PK6(ADC14/PCINT22)_83") (pintype "bidirectional"))
      (node (ref "PORTK") (pin "7") (pinfunction "7_7") (pintype "passive"))
    )
    (net (code "69") (name "/PK7") (class "Default")
      (node (ref "ATMEGA2560") (pin "82") (pinfunction "PK7(ADC15/PCINT23)_82") (pintype "bidirectional"))
      (node (ref "PORTK") (pin "8") (pinfunction "8_8") (pintype "passive"))
    )
    (net (code "70") (name "/PL0") (class "Default")
      (node (ref "ATMEGA2560") (pin "35") (pinfunction "PL0(ICP4)_35") (pintype "bidirectional"))
      (node (ref "PORTL") (pin "1") (pinfunction "1_1") (pintype "passive"))
    )
    (net (code "71") (name "/PL1") (class "Default")
      (node (ref "ATMEGA2560") (pin "36") (pinfunction "PL1(ICP5)_36") (pintype "bidirectional"))
      (node (ref "PORTL") (pin "2") (pinfunction "2_2") (pintype "passive"))
    )
    (net (code "72") (name "/PL2") (class "Default")
      (node (ref "ATMEGA2560") (pin "37") (pinfunction "PL2(T5)_37") (pintype "bidirectional"))
      (node (ref "PORTL") (pin "3") (pinfunction "3_3") (pintype "passive"))
    )
    (net (code "73") (name "/PL3") (class "Default")
      (node (ref "ATMEGA2560") (pin "38") (pinfunction "PL3(OC5A)_38") (pintype "bidirectional"))
      (node (ref "ESC_FR") (pin "1") (pinfunction "1_1") (pintype "passive"))
      (node (ref "PORTL") (pin "4") (pinfunction "4_4") (pintype "passive"))
    )
    (net (code "74") (name "/PL4") (class "Default")
      (node (ref "ATMEGA2560") (pin "39") (pinfunction "PL4(OC5B)_39") (pintype "bidirectional"))
      (node (ref "ESC_BR") (pin "1") (pinfunction "1_1") (pintype "passive"))
      (node (ref "PORTL") (pin "5") (pinfunction "5_5") (pintype "passive"))
    )
    (net (code "75") (name "/PL5") (class "Default")
      (node (ref "ATMEGA2560") (pin "40") (pinfunction "PL5(OC5C)_40") (pintype "bidirectional"))
      (node (ref "PORTL") (pin "6") (pinfunction "6_6") (pintype "passive"))
    )
    (net (code "76") (name "/PL6") (class "Default")
      (node (ref "ATMEGA2560") (pin "41") (pinfunction "PL6_41") (pintype "bidirectional"))
      (node (ref "PORTL") (pin "7") (pinfunction "7_7") (pintype "passive"))
    )
    (net (code "77") (name "/PL7") (class "Default")
      (node (ref "ATMEGA2560") (pin "42") (pinfunction "PL7_42") (pintype "bidirectional"))
      (node (ref "PORTL") (pin "8") (pinfunction "8_8") (pintype "passive"))
    )
    (net (code "78") (name "/RESET") (class "Default")
      (node (ref "ATMEGA2560") (pin "30") (pinfunction "RESET_30") (pintype "input"))
      (node (ref "C_RES") (pin "1") (pinfunction "1_1") (pintype "passive"))
      (node (ref "D_PD_RES") (pin "C") (pinfunction "C_C") (pintype "passive"))
      (node (ref "D_PU_RES") (pin "A") (pinfunction "A_A") (pintype "passive"))
      (node (ref "RSPI2") (pin "1") (pinfunction "1_1") (pintype "passive"))
      (node (ref "RSPI7") (pin "1") (pinfunction "1_1") (pintype "passive"))
      (node (ref "R_PU_RES") (pin "1") (pinfunction "1_1") (pintype "passive"))
      (node (ref "R_RES") (pin "1") (pinfunction "1_1") (pintype "passive"))
    )
    (net (code "79") (name "/SCK") (class "Default")
      (node (ref "ATMEGA2560") (pin "20") (pinfunction "(SCK/PCINT1)PB1_20") (pintype "bidirectional"))
      (node (ref "PORTB") (pin "2") (pinfunction "2_2") (pintype "passive"))
      (node (ref "RSPI3") (pin "1") (pinfunction "1_1") (pintype "passive"))
      (node (ref "RSPI6") (pin "1") (pinfunction "1_1") (pintype "passive"))
    )
    (net (code "80") (name "/SCL") (class "Default")
      (node (ref "ATMEGA2560") (pin "43") (pinfunction "(SCL/INT0)PD0_43") (pintype "bidirectional"))
      (node (ref "BQ76925") (pin "19") (pinfunction "SCL_19") (pintype "input"))
      (node (ref "I2C") (pin "3") (pinfunction "3_3") (pintype "passive"))
      (node (ref "IMU_BOARD") (pin "3") (pinfunction "3_3") (pintype "passive"))
      (node (ref "PORTD") (pin "1") (pinfunction "1_1") (pintype "passive"))
      (node (ref "RSCL") (pin "2") (pinfunction "2_2") (pintype "passive"))
    )
    (net (code "81") (name "/SDA") (class "Default")
      (node (ref "ATMEGA2560") (pin "44") (pinfunction "(SDA/INT1)PD1_44") (pintype "bidirectional"))
      (node (ref "BQ76925") (pin "18") (pinfunction "SDA_18") (pintype "bidirectional"))
      (node (ref "I2C") (pin "2") (pinfunction "2_2") (pintype "passive"))
      (node (ref "IMU_BOARD") (pin "4") (pinfunction "4_4") (pintype "passive"))
      (node (ref "PORTD") (pin "2") (pinfunction "2_2") (pintype "passive"))
      (node (ref "RSDA") (pin "2") (pinfunction "2_2") (pintype "passive"))
    )
    (net (code "82") (name "/SS") (class "Default")
      (node (ref "ATMEGA2560") (pin "19") (pinfunction "(SS/PCINT0)PB0_19") (pintype "bidirectional"))
      (node (ref "PORTB") (pin "1") (pinfunction "1_1") (pintype "passive"))
      (node (ref "R_PU_SS") (pin "1") (pinfunction "1_1") (pintype "passive"))
    )
    (net (code "83") (name "GND") (class "Default")
      (node (ref "ATMEGA2560") (pin "11") (pinfunction "GND_11") (pintype "power_in"))
      (node (ref "ATMEGA2560") (pin "32") (pinfunction "GND1_32") (pintype "power_in"))
      (node (ref "ATMEGA2560") (pin "62") (pinfunction "GND2_62") (pintype "power_in"))
      (node (ref "ATMEGA2560") (pin "81") (pinfunction "GND3_81") (pintype "power_in"))
      (node (ref "ATMEGA2560") (pin "99") (pinfunction "AGND_99") (pintype "power_in"))
      (node (ref "BAT-MONIT") (pin "P$1") (pinfunction "P$1_P$1") (pintype "bidirectional"))
      (node (ref "BQ76925") (pin "10") (pinfunction "VSS_10") (pintype "power_in"))
      (node (ref "BUZZ") (pin "+") (pinfunction "1_+") (pintype "passive"))
      (node (ref "CBAT") (pin "2") (pinfunction "2_2") (pintype "passive"))
      (node (ref "CIN") (pin "2") (pinfunction "2_2") (pintype "passive"))
      (node (ref "CIN1") (pin "2") (pinfunction "2_2") (pintype "passive"))
      (node (ref "CIN2") (pin "2") (pinfunction "2_2") (pintype "passive"))
      (node (ref "CIN3") (pin "2") (pinfunction "2_2") (pintype "passive"))
      (node (ref "CIN4") (pin "2") (pinfunction "2_2") (pintype "passive"))
      (node (ref "CIN5") (pin "2") (pinfunction "2_2") (pintype "passive"))
      (node (ref "CIN6") (pin "2") (pinfunction "2_2") (pintype "passive"))
      (node (ref "CI_10") (pin "2") (pinfunction "2_2") (pintype "passive"))
      (node (ref "CI_78") (pin "2") (pinfunction "2_2") (pintype "passive"))
      (node (ref "COUT") (pin "2") (pinfunction "2_2") (pintype "passive"))
      (node (ref "COUT2") (pin "2") (pinfunction "2_2") (pintype "passive"))
      (node (ref "CO_10") (pin "2") (pinfunction "2_2") (pintype "passive"))
      (node (ref "CO_78") (pin "2") (pinfunction "2_2") (pintype "passive"))
      (node (ref "CREF") (pin "2") (pinfunction "2_2") (pintype "passive"))
      (node (ref "CV3P3") (pin "2") (pinfunction "2_2") (pintype "passive"))
      (node (ref "C_AREF") (pin "2") (pinfunction "2_2") (pintype "passive"))
      (node (ref "C_AVCC") (pin "2") (pinfunction "2_2") (pintype "passive"))
      (node (ref "C_CRY1") (pin "1") (pinfunction "1_1") (pintype "passive"))
      (node (ref "C_CRY2") (pin "1") (pinfunction "1_1") (pintype "passive"))
      (node (ref "C_DECO1") (pin "2") (pinfunction "2_2") (pintype "passive"))
      (node (ref "C_DECO2") (pin "2") (pinfunction "2_2") (pintype "passive"))
      (node (ref "C_DECO3") (pin "2") (pinfunction "2_2") (pintype "passive"))
      (node (ref "C_DECO4") (pin "2") (pinfunction "2_2") (pintype "passive"))
      (node (ref "C_RES") (pin "2") (pinfunction "2_2") (pintype "passive"))
      (node (ref "D_PD_RES") (pin "A") (pinfunction "A_A") (pintype "passive"))
      (node (ref "ESC_BL") (pin "2") (pinfunction "2_2") (pintype "passive"))
      (node (ref "ESC_BR") (pin "2") (pinfunction "2_2") (pintype "passive"))
      (node (ref "ESC_FL") (pin "2") (pinfunction "2_2") (pintype "passive"))
      (node (ref "ESC_FR") (pin "2") (pinfunction "2_2") (pintype "passive"))
      (node (ref "EXTRA_5V") (pin "2") (pinfunction "2_2") (pintype "bidirectional"))
      (node (ref "EXTRA_5V") (pin "4") (pinfunction "4_4") (pintype "bidirectional"))
      (node (ref "EXTRA_5V") (pin "6") (pinfunction "6_6") (pintype "bidirectional"))
      (node (ref "I2C") (pin "4") (pinfunction "4_4") (pintype "passive"))
      (node (ref "IMU_BOARD") (pin "1") (pinfunction "1_1") (pintype "passive"))
      (node (ref "IMU_BOARD") (pin "5") (pinfunction "5_5") (pintype "passive"))
      (node (ref "INV") (pin "3") (pinfunction "GND_3") (pintype "bidirectional"))
      (node (ref "LM7805") (pin "2") (pinfunction "GND_2") (pintype "bidirectional"))
      (node (ref "LM7805") (pin "4") (pinfunction "GND_4") (pintype "bidirectional"))
      (node (ref "PORTA") (pin "9") (pinfunction "9_9") (pintype "passive"))
      (node (ref "PORTB") (pin "9") (pinfunction "9_9") (pintype "passive"))
      (node (ref "PORTD") (pin "9") (pinfunction "9_9") (pintype "passive"))
      (node (ref "PORTE") (pin "9") (pinfunction "9_9") (pintype "passive"))
      (node (ref "PORTF") (pin "9") (pinfunction "9_9") (pintype "passive"))
      (node (ref "PORTG") (pin "7") (pinfunction "7_7") (pintype "passive"))
      (node (ref "PORTG") (pin "9") (pinfunction "9_9") (pintype "passive"))
      (node (ref "PORTH") (pin "9") (pinfunction "9_9") (pintype "passive"))
      (node (ref "PORTJ") (pin "9") (pinfunction "9_9") (pintype "passive"))
      (node (ref "PORTK") (pin "9") (pinfunction "9_9") (pintype "passive"))
      (node (ref "PORTL") (pin "9") (pinfunction "9_9") (pintype "passive"))
      (node (ref "PROGRAMMER10") (pin "10") (pinfunction "10_10") (pintype "passive"))
      (node (ref "PROGRAMMER10") (pin "4") (pinfunction "4_4") (pintype "passive"))
      (node (ref "PROGRAMMER10") (pin "6") (pinfunction "6_6") (pintype "passive"))
      (node (ref "PROGRAMMER10") (pin "8") (pinfunction "8_8") (pintype "passive"))
      (node (ref "Q_SEL2") (pin "2") (pinfunction "S_2") (pintype "passive"))
      (node (ref "R2_10") (pin "1") (pinfunction "1_1") (pintype "passive"))
      (node (ref "RADIO_CONTROLLER") (pin "1") (pinfunction "GND_1") (pintype "power_in"))
      (node (ref "RADIO_CONTROLLER") (pin "2") (pinfunction "GND_2") (pintype "power_in"))
      (node (ref "RADIO_CONTROLLER") (pin "3") (pinfunction "GND_3") (pintype "power_in"))
      (node (ref "RADIO_CONTROLLER") (pin "4") (pinfunction "GND_4") (pintype "power_in"))
      (node (ref "RADIO_CONTROLLER") (pin "5") (pinfunction "GND_5") (pintype "power_in"))
      (node (ref "RADIO_CONTROLLER") (pin "6") (pinfunction "GND_6") (pintype "power_in"))
      (node (ref "RADIO_CONTROLLER") (pin "7") (pinfunction "GND_7") (pintype "power_in"))
      (node (ref "RES_SW") (pin "3") (pinfunction "2_3") (pintype "passive"))
      (node (ref "RES_SW") (pin "4") (pinfunction "2_4") (pintype "passive"))
      (node (ref "RIN") (pin "1") (pinfunction "1_1") (pintype "passive"))
      (node (ref "RLED0") (pin "2") (pinfunction "2_2") (pintype "passive"))
      (node (ref "RLED1") (pin "2") (pinfunction "2_2") (pintype "passive"))
      (node (ref "RLED2") (pin "2") (pinfunction "2_2") (pintype "passive"))
      (node (ref "RLED3") (pin "2") (pinfunction "2_2") (pintype "passive"))
      (node (ref "RLED4") (pin "2") (pinfunction "2_2") (pintype "passive"))
      (node (ref "RLED5") (pin "2") (pinfunction "2_2") (pintype "passive"))
      (node (ref "RLED6") (pin "2") (pinfunction "2_2") (pintype "passive"))
      (node (ref "RLED7") (pin "2") (pinfunction "2_2") (pintype "passive"))
      (node (ref "R_BAT") (pin "2") (pinfunction "2_2") (pintype "passive"))
      (node (ref "R_LCD2") (pin "1") (pinfunction "1_1") (pintype "passive"))
      (node (ref "R_PD_SEL") (pin "1") (pinfunction "1_1") (pintype "passive"))
      (node (ref "R_USB") (pin "2") (pinfunction "2_2") (pintype "passive"))
      (node (ref "R_VCC") (pin "2") (pinfunction "2_2") (pintype "passive"))
      (node (ref "SPI") (pin "6") (pinfunction "6_6") (pintype "bidirectional"))
    )
    (net (code "84") (name "GND-ISO") (class "Default")
      (node (ref "BAT-1") (pin "IN") (pinfunction "PAD_IN") (pintype "bidirectional"))
      (node (ref "BAT-2") (pin "IN") (pinfunction "PAD_IN") (pintype "bidirectional"))
      (node (ref "BAT-3") (pin "IN") (pinfunction "PAD_IN") (pintype "bidirectional"))
      (node (ref "BAT-4") (pin "IN") (pinfunction "PAD_IN") (pintype "bidirectional"))
      (node (ref "RSENSE") (pin "1") (pinfunction "1_1") (pintype "passive"))
      (node (ref "RSENSEN") (pin "1") (pinfunction "1_1") (pintype "passive"))
    )
    (net (code "85") (name "Net-(ATMEGA2560-(A8)PC0)") (class "Default")
      (node (ref "ATMEGA2560") (pin "53") (pinfunction "(A8)PC0_53") (pintype "bidirectional"))
      (node (ref "LED0") (pin "A") (pinfunction "A_A") (pintype "passive"))
    )
    (net (code "86") (name "Net-(ATMEGA2560-(A9)PC1)") (class "Default")
      (node (ref "ATMEGA2560") (pin "54") (pinfunction "(A9)PC1_54") (pintype "bidirectional"))
      (node (ref "LED1") (pin "A") (pinfunction "A_A") (pintype "passive"))
    )
    (net (code "87") (name "Net-(ATMEGA2560-(A10)PC2)") (class "Default")
      (node (ref "ATMEGA2560") (pin "55") (pinfunction "(A10)PC2_55") (pintype "bidirectional"))
      (node (ref "LED2") (pin "A") (pinfunction "A_A") (pintype "passive"))
    )
    (net (code "88") (name "Net-(ATMEGA2560-(A11)PC3)") (class "Default")
      (node (ref "ATMEGA2560") (pin "56") (pinfunction "(A11)PC3_56") (pintype "bidirectional"))
      (node (ref "LED3") (pin "A") (pinfunction "A_A") (pintype "passive"))
    )
    (net (code "89") (name "Net-(ATMEGA2560-(A12)PC4)") (class "Default")
      (node (ref "ATMEGA2560") (pin "57") (pinfunction "(A12)PC4_57") (pintype "bidirectional"))
      (node (ref "LED4") (pin "A") (pinfunction "A_A") (pintype "passive"))
    )
    (net (code "90") (name "Net-(ATMEGA2560-(A13)PC5)") (class "Default")
      (node (ref "ATMEGA2560") (pin "58") (pinfunction "(A13)PC5_58") (pintype "bidirectional"))
      (node (ref "LED5") (pin "A") (pinfunction "A_A") (pintype "passive"))
    )
    (net (code "91") (name "Net-(ATMEGA2560-(A14)PC6)") (class "Default")
      (node (ref "ATMEGA2560") (pin "59") (pinfunction "(A14)PC6_59") (pintype "bidirectional"))
      (node (ref "LED6") (pin "A") (pinfunction "A_A") (pintype "passive"))
    )
    (net (code "92") (name "Net-(ATMEGA2560-(A15)PC7)") (class "Default")
      (node (ref "ATMEGA2560") (pin "60") (pinfunction "(A15)PC7_60") (pintype "bidirectional"))
      (node (ref "LED7") (pin "A") (pinfunction "A_A") (pintype "passive"))
    )
    (net (code "93") (name "Net-(ATMEGA2560-AREF)") (class "Default")
      (node (ref "ATMEGA2560") (pin "98") (pinfunction "AREF_98") (pintype "bidirectional"))
      (node (ref "C_AREF") (pin "1") (pinfunction "1_1") (pintype "passive"))
    )
    (net (code "94") (name "Net-(ATMEGA2560-AVCC)") (class "Default")
      (node (ref "ATMEGA2560") (pin "100") (pinfunction "AVCC_100") (pintype "power_in"))
      (node (ref "C_AVCC") (pin "1") (pinfunction "1_1") (pintype "passive"))
      (node (ref "L1") (pin "2") (pinfunction "2_2") (pintype "passive"))
    )
    (net (code "95") (name "Net-(ATMEGA2560-XTAL1)") (class "Default")
      (node (ref "16MHZ") (pin "1") (pinfunction "1_1") (pintype "passive"))
      (node (ref "ATMEGA2560") (pin "34") (pinfunction "XTAL1_34") (pintype "input"))
      (node (ref "C_CRY1") (pin "2") (pinfunction "2_2") (pintype "passive"))
    )
    (net (code "96") (name "Net-(ATMEGA2560-XTAL2)") (class "Default")
      (node (ref "16MHZ") (pin "2") (pinfunction "2_2") (pintype "passive"))
      (node (ref "ATMEGA2560") (pin "33") (pinfunction "XTAL2_33") (pintype "output"))
      (node (ref "C_CRY2") (pin "2") (pinfunction "2_2") (pintype "passive"))
    )
    (net (code "97") (name "Net-(BAT-MONIT-PadP$2)") (class "Default")
      (node (ref "BAT-MONIT") (pin "P$2") (pinfunction "P$2_P$2") (pintype "bidirectional"))
      (node (ref "RIN1") (pin "1") (pinfunction "1_1") (pintype "passive"))
    )
    (net (code "98") (name "Net-(BAT-MONIT-PadP$3)") (class "Default")
      (node (ref "BAT-MONIT") (pin "P$3") (pinfunction "P$3_P$3") (pintype "bidirectional"))
      (node (ref "RIN2") (pin "1") (pinfunction "1_1") (pintype "passive"))
    )
    (net (code "99") (name "Net-(BAT-MONIT-PadP$4)") (class "Default")
      (node (ref "BAT-MONIT") (pin "P$4") (pinfunction "P$4_P$4") (pintype "bidirectional"))
      (node (ref "JP4") (pin "1") (pinfunction "1_1") (pintype "passive"))
      (node (ref "RIN3") (pin "1") (pinfunction "1_1") (pintype "passive"))
    )
    (net (code "100") (name "Net-(BAT-MONIT-PadP$5)") (class "Default")
      (node (ref "BAT-MONIT") (pin "P$5") (pinfunction "P$5_P$5") (pintype "bidirectional"))
      (node (ref "JP4") (pin "2") (pinfunction "2_2") (pintype "passive"))
      (node (ref "JP5") (pin "1") (pinfunction "1_1") (pintype "passive"))
      (node (ref "RIN4") (pin "1") (pinfunction "1_1") (pintype "passive"))
    )
    (net (code "101") (name "Net-(BAT-MONIT-PadP$6)") (class "Default")
      (node (ref "BAT-MONIT") (pin "P$6") (pinfunction "P$6_P$6") (pintype "bidirectional"))
      (node (ref "JP5") (pin "2") (pinfunction "2_2") (pintype "passive"))
      (node (ref "JP6") (pin "1") (pinfunction "1_1") (pintype "passive"))
      (node (ref "RIN5") (pin "1") (pinfunction "1_1") (pintype "passive"))
    )
    (net (code "102") (name "Net-(BAT-PadC)") (class "Default")
      (node (ref "BAT") (pin "C") (pinfunction "C_C") (pintype "passive"))
      (node (ref "R_BAT") (pin "1") (pinfunction "1_1") (pintype "passive"))
    )
    (net (code "103") (name "Net-(BQ76925-BAT)") (class "Default")
      (node (ref "BQ76925") (pin "1") (pinfunction "VCTL_1") (pintype "output"))
      (node (ref "BQ76925") (pin "2") (pinfunction "BAT_2") (pintype "power_in"))
      (node (ref "CBAT") (pin "1") (pinfunction "1_1") (pintype "passive"))
      (node (ref "RBAT") (pin "2") (pinfunction "2_2") (pintype "passive"))
    )
    (net (code "104") (name "Net-(BQ76925-SENSEN)") (class "Default")
      (node (ref "BQ76925") (pin "11") (pinfunction "SENSEN_11") (pintype "input"))
      (node (ref "CSENSE") (pin "1") (pinfunction "1_1") (pintype "passive"))
      (node (ref "RSENSEN") (pin "2") (pinfunction "2_2") (pintype "passive"))
    )
    (net (code "105") (name "Net-(BQ76925-SENSEP)") (class "Default")
      (node (ref "BQ76925") (pin "12") (pinfunction "SENSEP_12") (pintype "input"))
      (node (ref "CSENSE") (pin "2") (pinfunction "2_2") (pintype "passive"))
      (node (ref "RSENSEP") (pin "2") (pinfunction "2_2") (pintype "passive"))
    )
    (net (code "106") (name "Net-(BQ76925-VC0)") (class "Default")
      (node (ref "BQ76925") (pin "9") (pinfunction "VC0_9") (pintype "input"))
      (node (ref "CIN") (pin "1") (pinfunction "1_1") (pintype "passive"))
      (node (ref "RIN") (pin "2") (pinfunction "2_2") (pintype "passive"))
    )
    (net (code "107") (name "Net-(BQ76925-VC1)") (class "Default")
      (node (ref "BQ76925") (pin "8") (pinfunction "VC1_8") (pintype "input"))
      (node (ref "CIN1") (pin "1") (pinfunction "1_1") (pintype "passive"))
      (node (ref "RIN1") (pin "2") (pinfunction "2_2") (pintype "passive"))
    )
    (net (code "108") (name "Net-(BQ76925-VC2)") (class "Default")
      (node (ref "BQ76925") (pin "7") (pinfunction "VC2_7") (pintype "input"))
      (node (ref "CIN2") (pin "1") (pinfunction "1_1") (pintype "passive"))
      (node (ref "RIN2") (pin "2") (pinfunction "2_2") (pintype "passive"))
    )
    (net (code "109") (name "Net-(BQ76925-VC3)") (class "Default")
      (node (ref "BQ76925") (pin "6") (pinfunction "VC3_6") (pintype "input"))
      (node (ref "CIN3") (pin "1") (pinfunction "1_1") (pintype "passive"))
      (node (ref "RIN3") (pin "2") (pinfunction "2_2") (pintype "passive"))
    )
    (net (code "110") (name "Net-(BQ76925-VC4)") (class "Default")
      (node (ref "BQ76925") (pin "5") (pinfunction "VC4_5") (pintype "input"))
      (node (ref "CIN4") (pin "1") (pinfunction "1_1") (pintype "passive"))
      (node (ref "RIN4") (pin "2") (pinfunction "2_2") (pintype "passive"))
    )
    (net (code "111") (name "Net-(BQ76925-VC5)") (class "Default")
      (node (ref "BQ76925") (pin "4") (pinfunction "VC5_4") (pintype "input"))
      (node (ref "CIN5") (pin "1") (pinfunction "1_1") (pintype "passive"))
      (node (ref "RIN5") (pin "2") (pinfunction "2_2") (pintype "passive"))
    )
    (net (code "112") (name "Net-(BQ76925-VC6)") (class "Default")
      (node (ref "BQ76925") (pin "3") (pinfunction "VC6_3") (pintype "input"))
      (node (ref "CIN6") (pin "1") (pinfunction "1_1") (pintype "passive"))
      (node (ref "RIN6") (pin "2") (pinfunction "2_2") (pintype "passive"))
    )
    (net (code "113") (name "Net-(INV-Y)") (class "Default")
      (node (ref "INV") (pin "4") (pinfunction "Y_4") (pintype "bidirectional"))
      (node (ref "Q_SEL2") (pin "1") (pinfunction "G_1") (pintype "passive"))
      (node (ref "R_PD_SEL") (pin "2") (pinfunction "2_2") (pintype "passive"))
    )
    (net (code "114") (name "Net-(LED0-PadC)") (class "Default")
      (node (ref "LED0") (pin "C") (pinfunction "C_C") (pintype "passive"))
      (node (ref "RLED0") (pin "1") (pinfunction "1_1") (pintype "passive"))
    )
    (net (code "115") (name "Net-(LED1-PadC)") (class "Default")
      (node (ref "LED1") (pin "C") (pinfunction "C_C") (pintype "passive"))
      (node (ref "RLED1") (pin "1") (pinfunction "1_1") (pintype "passive"))
    )
    (net (code "116") (name "Net-(LED2-PadC)") (class "Default")
      (node (ref "LED2") (pin "C") (pinfunction "C_C") (pintype "passive"))
      (node (ref "RLED2") (pin "1") (pinfunction "1_1") (pintype "passive"))
    )
    (net (code "117") (name "Net-(LED3-PadC)") (class "Default")
      (node (ref "LED3") (pin "C") (pinfunction "C_C") (pintype "passive"))
      (node (ref "RLED3") (pin "1") (pinfunction "1_1") (pintype "passive"))
    )
    (net (code "118") (name "Net-(LED4-PadC)") (class "Default")
      (node (ref "LED4") (pin "C") (pinfunction "C_C") (pintype "passive"))
      (node (ref "RLED4") (pin "1") (pinfunction "1_1") (pintype "passive"))
    )
    (net (code "119") (name "Net-(LED5-PadC)") (class "Default")
      (node (ref "LED5") (pin "C") (pinfunction "C_C") (pintype "passive"))
      (node (ref "RLED5") (pin "1") (pinfunction "1_1") (pintype "passive"))
    )
    (net (code "120") (name "Net-(LED6-PadC)") (class "Default")
      (node (ref "LED6") (pin "C") (pinfunction "C_C") (pintype "passive"))
      (node (ref "RLED6") (pin "1") (pinfunction "1_1") (pintype "passive"))
    )
    (net (code "121") (name "Net-(LED7-PadC)") (class "Default")
      (node (ref "LED7") (pin "C") (pinfunction "C_C") (pintype "passive"))
      (node (ref "RLED7") (pin "1") (pinfunction "1_1") (pintype "passive"))
    )
    (net (code "122") (name "Net-(LM1085-ADJ{slash}GND)") (class "Default")
      (node (ref "LM1085") (pin "1") (pinfunction "ADJ/GND_1") (pintype "passive"))
      (node (ref "R2_10") (pin "2") (pinfunction "2_2") (pintype "passive"))
      (node (ref "R_10") (pin "2") (pinfunction "2_2") (pintype "passive"))
    )
    (net (code "123") (name "Net-(LM1085-EPAD)") (class "Default")
      (node (ref "CO_10") (pin "1") (pinfunction "1_1") (pintype "passive"))
      (node (ref "EXTRA_5V") (pin "1") (pinfunction "1_1") (pintype "bidirectional"))
      (node (ref "EXTRA_5V") (pin "3") (pinfunction "3_3") (pintype "bidirectional"))
      (node (ref "EXTRA_5V") (pin "5") (pinfunction "5_5") (pintype "bidirectional"))
      (node (ref "LM1085") (pin "2") (pinfunction "OUTPUT_2") (pintype "output"))
      (node (ref "LM1085") (pin "4") (pinfunction "EPAD_4") (pintype "passive"))
      (node (ref "R_10") (pin "1") (pinfunction "1_1") (pintype "passive"))
    )
    (net (code "124") (name "Net-(LM7805-IN)") (class "Default")
      (node (ref "CI_78") (pin "1") (pinfunction "1_1") (pintype "passive"))
      (node (ref "LM7805") (pin "1") (pinfunction "IN_1") (pintype "bidirectional"))
      (node (ref "Q_SEL1") (pin "2") (pinfunction "S_2") (pintype "passive"))
    )
    (net (code "125") (name "Net-(PROGRAMMER10-Pad1)") (class "Default")
      (node (ref "PROGRAMMER10") (pin "1") (pinfunction "1_1") (pintype "passive"))
      (node (ref "RSPI1") (pin "2") (pinfunction "2_2") (pintype "passive"))
    )
    (net (code "126") (name "Net-(PROGRAMMER10-Pad5)") (class "Default")
      (node (ref "PROGRAMMER10") (pin "5") (pinfunction "5_5") (pintype "passive"))
      (node (ref "RSPI2") (pin "2") (pinfunction "2_2") (pintype "passive"))
    )
    (net (code "127") (name "Net-(PROGRAMMER10-Pad7)") (class "Default")
      (node (ref "PROGRAMMER10") (pin "7") (pinfunction "7_7") (pintype "passive"))
      (node (ref "RSPI3") (pin "2") (pinfunction "2_2") (pintype "passive"))
    )
    (net (code "128") (name "Net-(PROGRAMMER10-Pad9)") (class "Default")
      (node (ref "PROGRAMMER10") (pin "9") (pinfunction "9_9") (pintype "passive"))
      (node (ref "RSPI4") (pin "2") (pinfunction "2_2") (pintype "passive"))
    )
    (net (code "129") (name "Net-(Q_SEL1-G)") (class "Default")
      (node (ref "Q_SEL1") (pin "1") (pinfunction "G_1") (pintype "passive"))
      (node (ref "Q_SEL2") (pin "3") (pinfunction "D_3") (pintype "passive"))
      (node (ref "R_PU_SEL") (pin "1") (pinfunction "1_1") (pintype "passive"))
    )
    (net (code "130") (name "Net-(RES_SW-1-Pad2)") (class "Default")
      (node (ref "RES_SW") (pin "1") (pinfunction "1_1") (pintype "passive"))
      (node (ref "RES_SW") (pin "2") (pinfunction "1_2") (pintype "passive"))
      (node (ref "R_RES") (pin "2") (pinfunction "2_2") (pintype "passive"))
    )
    (net (code "131") (name "Net-(RSPI5-Pad2)") (class "Default")
      (node (ref "RSPI5") (pin "2") (pinfunction "2_2") (pintype "passive"))
      (node (ref "SPI") (pin "1") (pinfunction "1_1") (pintype "bidirectional"))
    )
    (net (code "132") (name "Net-(RSPI6-Pad2)") (class "Default")
      (node (ref "RSPI6") (pin "2") (pinfunction "2_2") (pintype "passive"))
      (node (ref "SPI") (pin "3") (pinfunction "3_3") (pintype "bidirectional"))
    )
    (net (code "133") (name "Net-(RSPI7-Pad2)") (class "Default")
      (node (ref "RSPI7") (pin "2") (pinfunction "2_2") (pintype "passive"))
      (node (ref "SPI") (pin "5") (pinfunction "5_5") (pintype "bidirectional"))
    )
    (net (code "134") (name "Net-(RSPI8-Pad2)") (class "Default")
      (node (ref "RSPI8") (pin "2") (pinfunction "2_2") (pintype "passive"))
      (node (ref "SPI") (pin "4") (pinfunction "4_4") (pintype "bidirectional"))
    )
    (net (code "135") (name "Net-(R_USB-Pad1)") (class "Default")
      (node (ref "R_USB") (pin "1") (pinfunction "1_1") (pintype "passive"))
      (node (ref "USB") (pin "C") (pinfunction "C_C") (pintype "passive"))
    )
    (net (code "136") (name "Net-(R_VCC-Pad1)") (class "Default")
      (node (ref "R_VCC") (pin "1") (pinfunction "1_1") (pintype "passive"))
      (node (ref "VCC") (pin "C") (pinfunction "C_C") (pintype "passive"))
    )
    (net (code "137") (name "VCC") (class "Default")
      (node (ref "ATMEGA2560") (pin "10") (pinfunction "VCC_10") (pintype "power_in"))
      (node (ref "ATMEGA2560") (pin "31") (pinfunction "VCC1_31") (pintype "power_in"))
      (node (ref "ATMEGA2560") (pin "61") (pinfunction "VCC2_61") (pintype "power_in"))
      (node (ref "ATMEGA2560") (pin "80") (pinfunction "VCC3_80") (pintype "power_in"))
      (node (ref "CO_78") (pin "1") (pinfunction "1_1") (pintype "passive"))
      (node (ref "C_DECO1") (pin "1") (pinfunction "1_1") (pintype "passive"))
      (node (ref "C_DECO2") (pin "1") (pinfunction "1_1") (pintype "passive"))
      (node (ref "C_DECO3") (pin "1") (pinfunction "1_1") (pintype "passive"))
      (node (ref "C_DECO4") (pin "1") (pinfunction "1_1") (pintype "passive"))
      (node (ref "D_PU_RES") (pin "C") (pinfunction "C_C") (pintype "passive"))
      (node (ref "D_SEL") (pin "C") (pinfunction "C_C") (pintype "passive"))
      (node (ref "I2C") (pin "1") (pinfunction "1_1") (pintype "passive"))
      (node (ref "IMU_BOARD") (pin "6") (pinfunction "6_6") (pintype "passive"))
      (node (ref "INV") (pin "5") (pinfunction "VCC_5") (pintype "bidirectional"))
      (node (ref "L1") (pin "1") (pinfunction "1_1") (pintype "passive"))
      (node (ref "LM7805") (pin "3") (pinfunction "OUT_3") (pintype "bidirectional"))
      (node (ref "PORTB") (pin "10") (pinfunction "10_10") (pintype "passive"))
      (node (ref "PORTD") (pin "10") (pinfunction "10_10") (pintype "passive"))
      (node (ref "PORTE") (pin "10") (pinfunction "10_10") (pintype "passive"))
      (node (ref "PORTF") (pin "10") (pinfunction "10_10") (pintype "passive"))
      (node (ref "PORTG") (pin "10") (pinfunction "10_10") (pintype "passive"))
      (node (ref "PORTH") (pin "10") (pinfunction "10_10") (pintype "passive"))
      (node (ref "PORTJ") (pin "10") (pinfunction "10_10") (pintype "passive"))
      (node (ref "PORTK") (pin "10") (pinfunction "10_10") (pintype "passive"))
      (node (ref "PORTL") (pin "10") (pinfunction "10_10") (pintype "passive"))
      (node (ref "RADIO_CONTROLLER") (pin "10") (pinfunction "5V_10") (pintype "power_in"))
      (node (ref "RADIO_CONTROLLER") (pin "11") (pinfunction "5V_11") (pintype "power_in"))
      (node (ref "RADIO_CONTROLLER") (pin "12") (pinfunction "5V_12") (pintype "power_in"))
      (node (ref "RADIO_CONTROLLER") (pin "13") (pinfunction "5V_13") (pintype "power_in"))
      (node (ref "RADIO_CONTROLLER") (pin "14") (pinfunction "5V_14") (pintype "power_in"))
      (node (ref "RADIO_CONTROLLER") (pin "8") (pinfunction "5V_8") (pintype "power_in"))
      (node (ref "RADIO_CONTROLLER") (pin "9") (pinfunction "5V_9") (pintype "power_in"))
      (node (ref "RSCL") (pin "1") (pinfunction "1_1") (pintype "passive"))
      (node (ref "RSDA") (pin "1") (pinfunction "1_1") (pintype "passive"))
      (node (ref "R_LCD1") (pin "2") (pinfunction "2_2") (pintype "passive"))
      (node (ref "R_PU_RES") (pin "2") (pinfunction "2_2") (pintype "passive"))
      (node (ref "R_PU_SS") (pin "2") (pinfunction "2_2") (pintype "passive"))
      (node (ref "VCC") (pin "A") (pinfunction "A_A") (pintype "passive"))
    )
    (net (code "138") (name "V_BATT") (class "Default")
      (node (ref "BAT-MONIT") (pin "P$7") (pinfunction "P$7_P$7") (pintype "bidirectional"))
      (node (ref "CI_10") (pin "1") (pinfunction "1_1") (pintype "passive"))
      (node (ref "JP6") (pin "2") (pinfunction "2_2") (pintype "passive"))
      (node (ref "LM1085") (pin "3") (pinfunction "INPUT_3") (pintype "input"))
      (node (ref "POWER_SWITCH") (pin "1") (pinfunction "O_1") (pintype "passive"))
      (node (ref "Q_SEL1") (pin "3") (pinfunction "D_3") (pintype "passive"))
      (node (ref "RBAT") (pin "1") (pinfunction "1_1") (pintype "passive"))
      (node (ref "RIN6") (pin "1") (pinfunction "1_1") (pintype "passive"))
      (node (ref "R_PU_SEL") (pin "2") (pinfunction "2_2") (pintype "passive"))
    )
    (net (code "139") (name "V_USB") (class "Default")
      (node (ref "D_SEL") (pin "A") (pinfunction "A_A") (pintype "passive"))
      (node (ref "INV") (pin "2") (pinfunction "A_2") (pintype "bidirectional"))
      (node (ref "PROGRAMMER10") (pin "2") (pinfunction "2_2") (pintype "passive"))
      (node (ref "SPI") (pin "2") (pinfunction "2_2") (pintype "bidirectional"))
      (node (ref "USB") (pin "A") (pinfunction "A_A") (pintype "passive"))
    )
    (net (code "140") (name "unconnected-(BQ76925-VTB-Pad16)") (class "Default")
      (node (ref "BQ76925") (pin "16") (pinfunction "VTB_16") (pintype "output"))
    )
    (net (code "141") (name "unconnected-(INV-NC-Pad1)") (class "Default")
      (node (ref "INV") (pin "1") (pinfunction "NC_1") (pintype "bidirectional"))
    )
    (net (code "142") (name "unconnected-(PROGRAMMER10-Pad3)") (class "Default")
      (node (ref "PROGRAMMER10") (pin "3") (pinfunction "3_3") (pintype "passive"))
    )
    (net (code "143") (name "unconnected-(RADIO_CONTROLLER-7-Pad21)") (class "Default")
      (node (ref "RADIO_CONTROLLER") (pin "21") (pinfunction "7_21") (pintype "bidirectional"))
    )
  )
)
